# 07_eMMC.net
KiCad netlist of a schematic drawn in Altium Designer
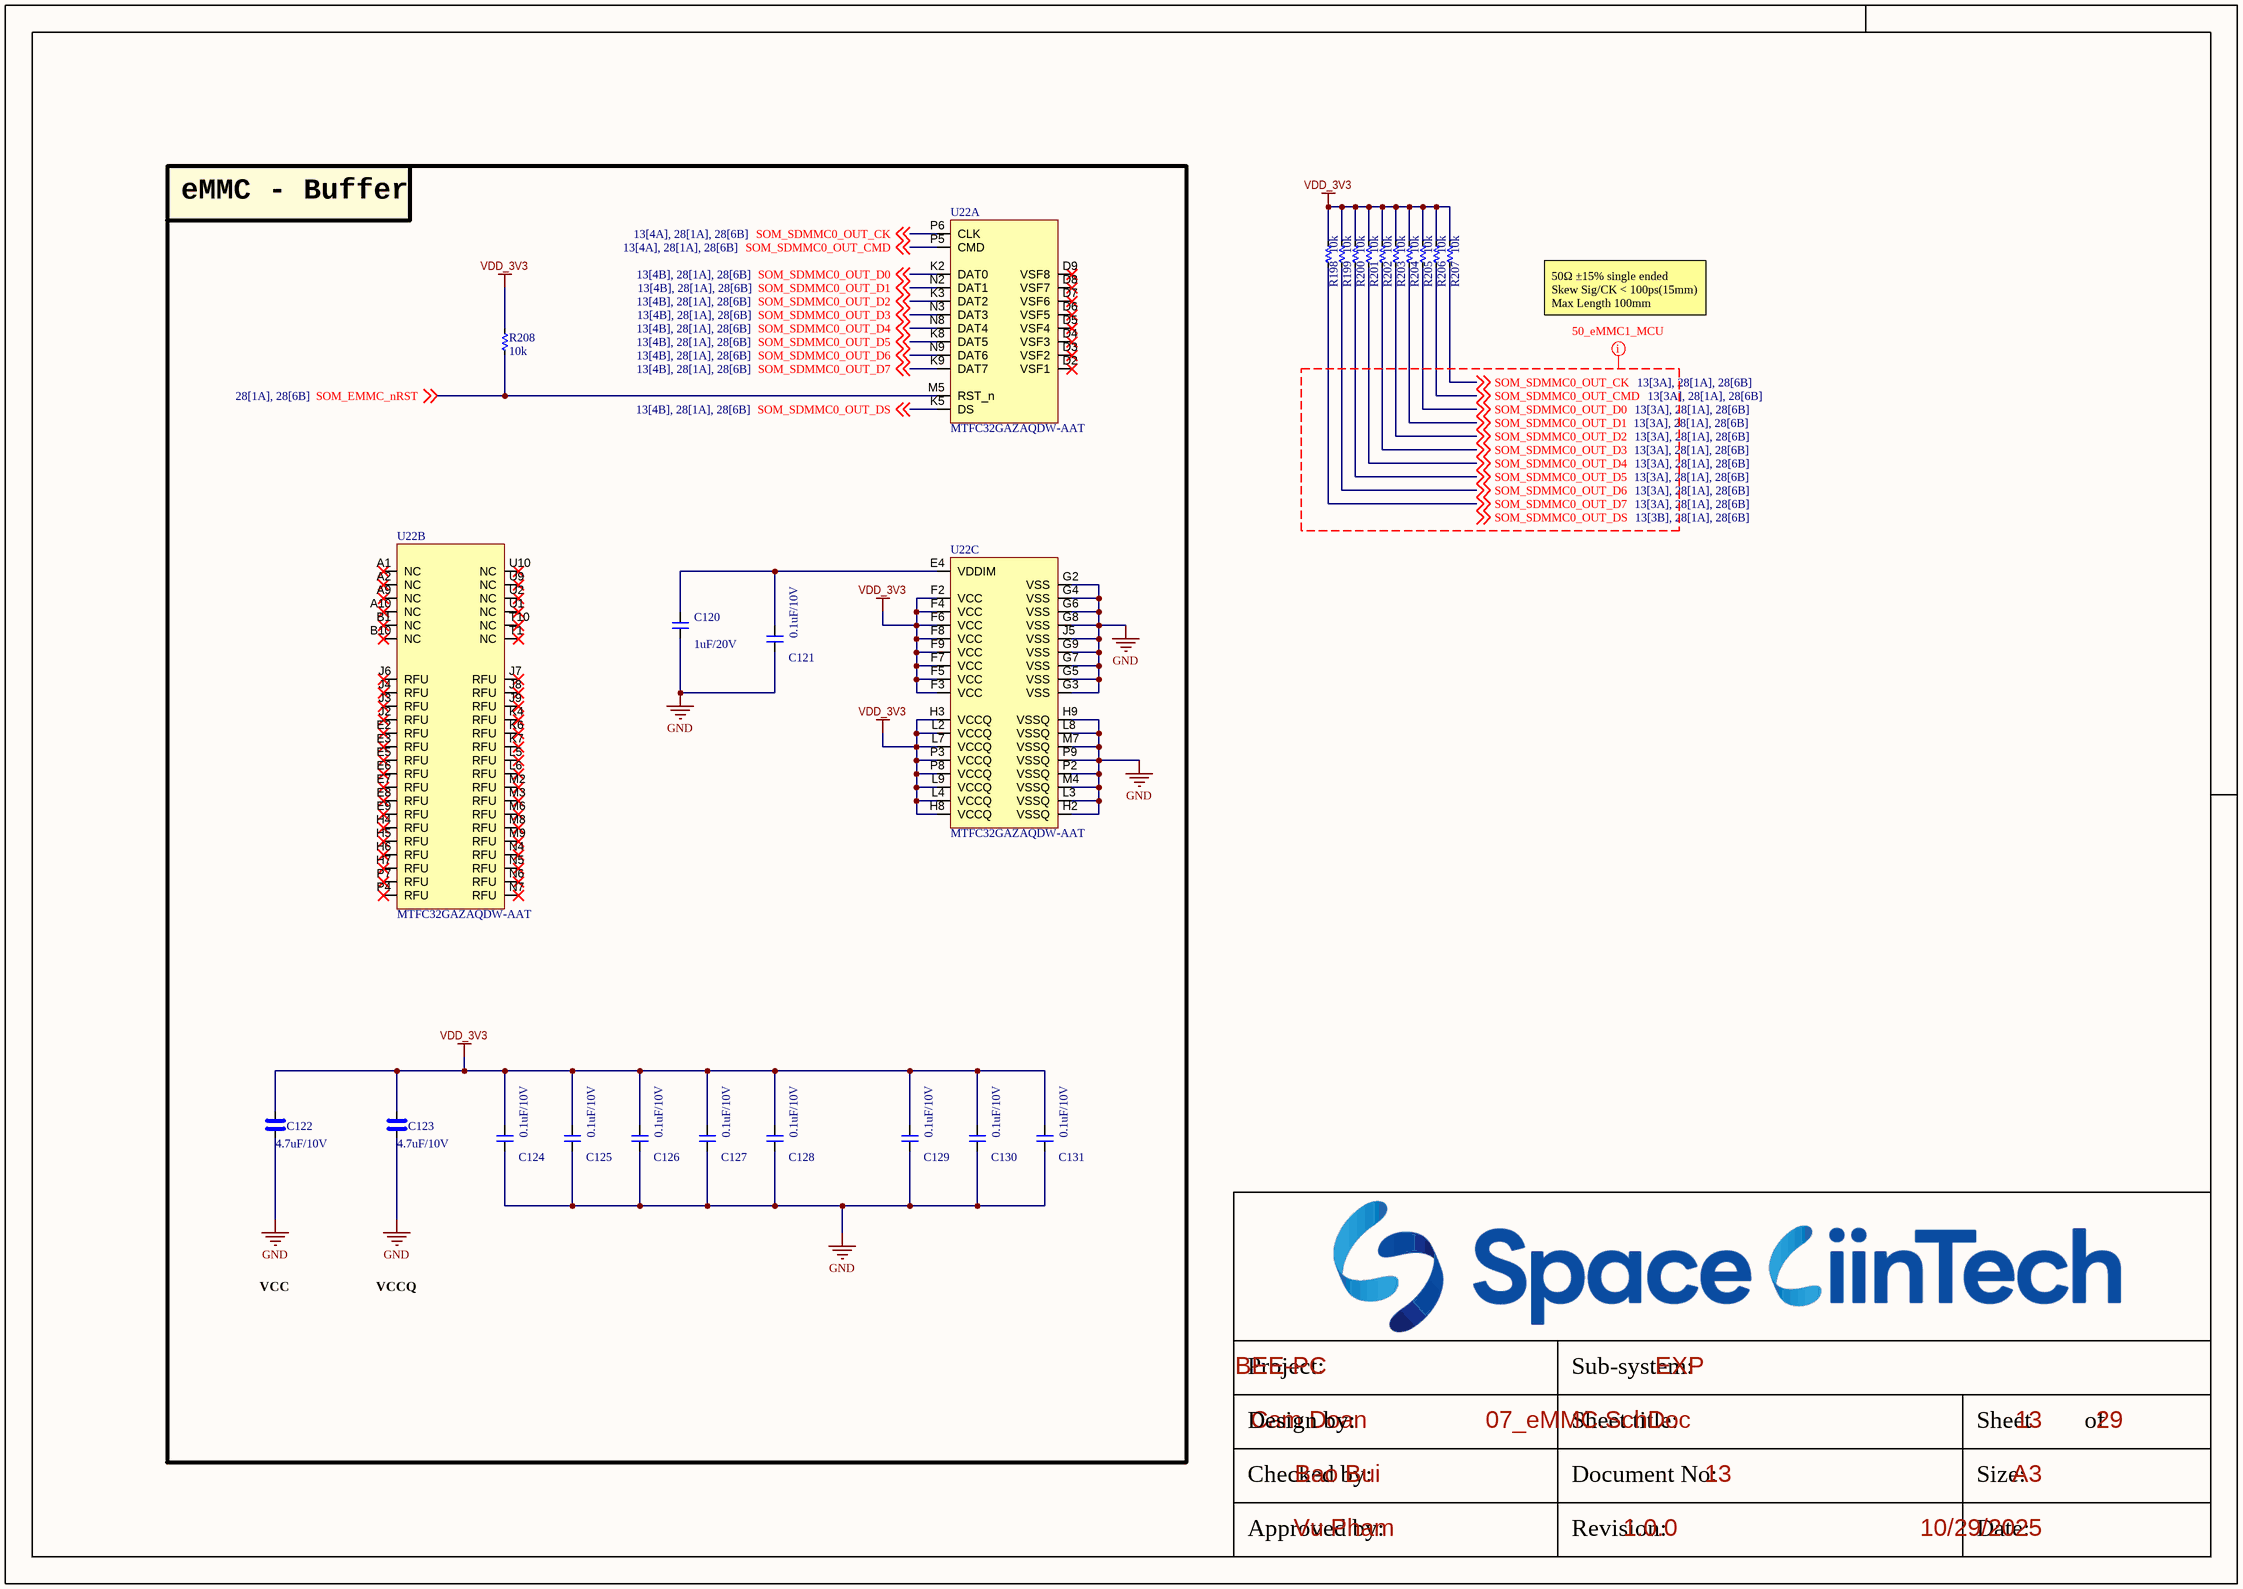
[diagram p0: 07_eMMC.SchDoc]

(export (version "E")
  (design (tool "Eeschema 10.0.6"))
  (components
    (comp (ref "C120")
      (value "1uF/20V")
      (footprint "CAP_C_1005X60")
      (description "CAP CHIP")
      (libsource (lib "LABLIB") (part "_CAP_C_2"))
    )
    (comp (ref "C121")
      (value "0.1uF/10V")
      (footprint "CAP_C_1005X60")
      (description "CAP CHIP")
      (libsource (lib "LABLIB") (part "_CAP_C_2"))
    )
    (comp (ref "C122")
      (value "4.7uF/10V")
      (footprint "CAP_C_1005X60")
      (description "CAP CHIP High Value")
      (libsource (lib "LABLIB") (part "_CAP_C_High_2"))
    )
    (comp (ref "C123")
      (value "4.7uF/10V")
      (footprint "CAP_C_1005X60")
      (description "CAP CHIP High Value")
      (libsource (lib "LABLIB") (part "_CAP_C_High_2"))
    )
    (comp (ref "C124")
      (value "0.1uF/10V")
      (footprint "CAP_C_1005X60")
      (description "CAP CHIP")
      (libsource (lib "LABLIB") (part "_CAP_C_2"))
    )
    (comp (ref "C125")
      (value "0.1uF/10V")
      (footprint "CAP_C_1005X60")
      (description "CAP CHIP")
      (libsource (lib "LABLIB") (part "_CAP_C_2"))
    )
    (comp (ref "C126")
      (value "0.1uF/10V")
      (footprint "CAP_C_1005X60")
      (description "CAP CHIP")
      (libsource (lib "LABLIB") (part "_CAP_C_2"))
    )
    (comp (ref "C127")
      (value "0.1uF/10V")
      (footprint "CAP_C_1005X60")
      (description "CAP CHIP")
      (libsource (lib "LABLIB") (part "_CAP_C_2"))
    )
    (comp (ref "C128")
      (value "0.1uF/10V")
      (footprint "CAP_C_1005X60")
      (description "CAP CHIP")
      (libsource (lib "LABLIB") (part "_CAP_C_2"))
    )
    (comp (ref "C129")
      (value "0.1uF/10V")
      (footprint "CAP_C_1005X60")
      (description "CAP CHIP")
      (libsource (lib "LABLIB") (part "_CAP_C_2"))
    )
    (comp (ref "C130")
      (value "0.1uF/10V")
      (footprint "CAP_C_1005X60")
      (description "CAP CHIP")
      (libsource (lib "LABLIB") (part "_CAP_C_2"))
    )
    (comp (ref "C131")
      (value "0.1uF/10V")
      (footprint "CAP_C_1005X60")
      (description "CAP CHIP")
      (libsource (lib "LABLIB") (part "_CAP_C_2"))
    )
    (comp (ref "R198")
      (value "10k")
      (footprint "RES_C_1005X40")
      (description "RES")
      (libsource (lib "LABLIB") (part "_RES_B_2"))
    )
    (comp (ref "R199")
      (value "10k")
      (footprint "RES_C_1005X40")
      (description "RES")
      (libsource (lib "LABLIB") (part "_RES_B_2"))
    )
    (comp (ref "R200")
      (value "10k")
      (footprint "RES_C_1005X40")
      (description "RES")
      (libsource (lib "LABLIB") (part "_RES_B_2"))
    )
    (comp (ref "R201")
      (value "10k")
      (footprint "RES_C_1005X40")
      (description "RES")
      (libsource (lib "LABLIB") (part "_RES_B_2"))
    )
    (comp (ref "R202")
      (value "10k")
      (footprint "RES_C_1005X40")
      (description "RES")
      (libsource (lib "LABLIB") (part "_RES_B_2"))
    )
    (comp (ref "R203")
      (value "10k")
      (footprint "RES_C_1005X40")
      (description "RES")
      (libsource (lib "LABLIB") (part "_RES_B_2"))
    )
    (comp (ref "R204")
      (value "10k")
      (footprint "RES_C_1005X40")
      (description "RES")
      (libsource (lib "LABLIB") (part "_RES_B_2"))
    )
    (comp (ref "R205")
      (value "10k")
      (footprint "RES_C_1005X40")
      (description "RES")
      (libsource (lib "LABLIB") (part "_RES_B_2"))
    )
    (comp (ref "R206")
      (value "10k")
      (footprint "RES_C_1005X40")
      (description "RES")
      (libsource (lib "LABLIB") (part "_RES_B_2"))
    )
    (comp (ref "R207")
      (value "10k")
      (footprint "RES_C_1005X40")
      (description "RES")
      (libsource (lib "LABLIB") (part "_RES_B_2"))
    )
    (comp (ref "R208")
      (value "10k")
      (footprint "RES_C_1005X40")
      (description "RES")
      (libsource (lib "LABLIB") (part "_RES_B_2"))
    )
    (comp (ref "U22")
      (value "MTFC32GAZAQDW-AAT")
      (footprint "BGA_100_C_100P_10X17_1400X1800X150")
      (libsource (lib "emmc_nofootprint") (part "MTFC32GAZAQDW-AAT"))
    )
  )
  (nets
    (net (code "1") (name "GND") (class "Default")
      (node (ref "C120") (pin "1") (pinfunction "1_1") (pintype "passive"))
      (node (ref "C121") (pin "1") (pinfunction "1_1") (pintype "passive"))
      (node (ref "C122") (pin "1") (pinfunction "1_1") (pintype "passive"))
      (node (ref "C123") (pin "1") (pinfunction "1_1") (pintype "passive"))
      (node (ref "C124") (pin "1") (pinfunction "1_1") (pintype "passive"))
      (node (ref "C125") (pin "1") (pinfunction "1_1") (pintype "passive"))
      (node (ref "C126") (pin "1") (pinfunction "1_1") (pintype "passive"))
      (node (ref "C127") (pin "1") (pinfunction "1_1") (pintype "passive"))
      (node (ref "C128") (pin "1") (pinfunction "1_1") (pintype "passive"))
      (node (ref "C129") (pin "1") (pinfunction "1_1") (pintype "passive"))
      (node (ref "C130") (pin "1") (pinfunction "1_1") (pintype "passive"))
      (node (ref "C131") (pin "1") (pinfunction "1_1") (pintype "passive"))
      (node (ref "U22") (pin "G2") (pinfunction "VSS_G2") (pintype "passive"))
      (node (ref "U22") (pin "G3") (pinfunction "VSS_G3") (pintype "passive"))
      (node (ref "U22") (pin "G4") (pinfunction "VSS_G4") (pintype "passive"))
      (node (ref "U22") (pin "G5") (pinfunction "VSS_G5") (pintype "passive"))
      (node (ref "U22") (pin "G6") (pinfunction "VSS_G6") (pintype "passive"))
      (node (ref "U22") (pin "G7") (pinfunction "VSS_G7") (pintype "passive"))
      (node (ref "U22") (pin "G8") (pinfunction "VSS_G8") (pintype "passive"))
      (node (ref "U22") (pin "G9") (pinfunction "VSS_G9") (pintype "passive"))
      (node (ref "U22") (pin "H2") (pinfunction "VSSQ_H2") (pintype "passive"))
      (node (ref "U22") (pin "H9") (pinfunction "VSSQ_H9") (pintype "passive"))
      (node (ref "U22") (pin "J5") (pinfunction "VSS_J5") (pintype "passive"))
      (node (ref "U22") (pin "L3") (pinfunction "VSSQ_L3") (pintype "passive"))
      (node (ref "U22") (pin "L8") (pinfunction "VSSQ_L8") (pintype "passive"))
      (node (ref "U22") (pin "M4") (pinfunction "VSSQ_M4") (pintype "passive"))
      (node (ref "U22") (pin "M7") (pinfunction "VSSQ_M7") (pintype "passive"))
      (node (ref "U22") (pin "P2") (pinfunction "VSSQ_P2") (pintype "passive"))
      (node (ref "U22") (pin "P9") (pinfunction "VSSQ_P9") (pintype "passive"))
    )
    (net (code "2") (name "Net-(U22C-VDDIM)") (class "Default")
      (node (ref "C120") (pin "2") (pinfunction "2_2") (pintype "passive"))
      (node (ref "C121") (pin "2") (pinfunction "2_2") (pintype "passive"))
      (node (ref "U22") (pin "E4") (pinfunction "VDDIM_E4") (pintype "passive"))
    )
    (net (code "3") (name "SOM_EMMC_nRST") (class "Default")
      (node (ref "R208") (pin "1") (pinfunction "1_1") (pintype "passive"))
      (node (ref "U22") (pin "M5") (pinfunction "RST_n_M5") (pintype "passive"))
    )
    (net (code "4") (name "SOM_SDMMC0_OUT_CK") (class "Default")
      (node (ref "R207") (pin "1") (pinfunction "1_1") (pintype "passive"))
      (node (ref "U22") (pin "P6") (pinfunction "CLK_P6") (pintype "passive"))
    )
    (net (code "5") (name "SOM_SDMMC0_OUT_CMD") (class "Default")
      (node (ref "R206") (pin "1") (pinfunction "1_1") (pintype "passive"))
      (node (ref "U22") (pin "P5") (pinfunction "CMD_P5") (pintype "passive"))
    )
    (net (code "6") (name "SOM_SDMMC0_OUT_D0") (class "Default")
      (node (ref "R205") (pin "1") (pinfunction "1_1") (pintype "passive"))
      (node (ref "U22") (pin "K2") (pinfunction "DAT0_K2") (pintype "passive"))
    )
    (net (code "7") (name "SOM_SDMMC0_OUT_D1") (class "Default")
      (node (ref "R204") (pin "1") (pinfunction "1_1") (pintype "passive"))
      (node (ref "U22") (pin "N2") (pinfunction "DAT1_N2") (pintype "passive"))
    )
    (net (code "8") (name "SOM_SDMMC0_OUT_D2") (class "Default")
      (node (ref "R203") (pin "1") (pinfunction "1_1") (pintype "passive"))
      (node (ref "U22") (pin "K3") (pinfunction "DAT2_K3") (pintype "passive"))
    )
    (net (code "9") (name "SOM_SDMMC0_OUT_D3") (class "Default")
      (node (ref "R202") (pin "1") (pinfunction "1_1") (pintype "passive"))
      (node (ref "U22") (pin "N3") (pinfunction "DAT3_N3") (pintype "passive"))
    )
    (net (code "10") (name "SOM_SDMMC0_OUT_D4") (class "Default")
      (node (ref "R201") (pin "1") (pinfunction "1_1") (pintype "passive"))
      (node (ref "U22") (pin "N8") (pinfunction "DAT4_N8") (pintype "passive"))
    )
    (net (code "11") (name "SOM_SDMMC0_OUT_D5") (class "Default")
      (node (ref "R200") (pin "1") (pinfunction "1_1") (pintype "passive"))
      (node (ref "U22") (pin "K8") (pinfunction "DAT5_K8") (pintype "passive"))
    )
    (net (code "12") (name "SOM_SDMMC0_OUT_D6") (class "Default")
      (node (ref "R199") (pin "1") (pinfunction "1_1") (pintype "passive"))
      (node (ref "U22") (pin "N9") (pinfunction "DAT6_N9") (pintype "passive"))
    )
    (net (code "13") (name "SOM_SDMMC0_OUT_D7") (class "Default")
      (node (ref "R198") (pin "1") (pinfunction "1_1") (pintype "passive"))
      (node (ref "U22") (pin "K9") (pinfunction "DAT7_K9") (pintype "passive"))
    )
    (net (code "14") (name "SOM_SDMMC0_OUT_DS") (class "Default")
      (node (ref "U22") (pin "K5") (pinfunction "DS_K5") (pintype "passive"))
    )
    (net (code "15") (name "VDD_3V3") (class "Default")
      (node (ref "C122") (pin "2") (pinfunction "2_2") (pintype "passive"))
      (node (ref "C123") (pin "2") (pinfunction "2_2") (pintype "passive"))
      (node (ref "C124") (pin "2") (pinfunction "2_2") (pintype "passive"))
      (node (ref "C125") (pin "2") (pinfunction "2_2") (pintype "passive"))
      (node (ref "C126") (pin "2") (pinfunction "2_2") (pintype "passive"))
      (node (ref "C127") (pin "2") (pinfunction "2_2") (pintype "passive"))
      (node (ref "C128") (pin "2") (pinfunction "2_2") (pintype "passive"))
      (node (ref "C129") (pin "2") (pinfunction "2_2") (pintype "passive"))
      (node (ref "C130") (pin "2") (pinfunction "2_2") (pintype "passive"))
      (node (ref "C131") (pin "2") (pinfunction "2_2") (pintype "passive"))
      (node (ref "R198") (pin "2") (pinfunction "2_2") (pintype "passive"))
      (node (ref "R199") (pin "2") (pinfunction "2_2") (pintype "passive"))
      (node (ref "R200") (pin "2") (pinfunction "2_2") (pintype "passive"))
      (node (ref "R201") (pin "2") (pinfunction "2_2") (pintype "passive"))
      (node (ref "R202") (pin "2") (pinfunction "2_2") (pintype "passive"))
      (node (ref "R203") (pin "2") (pinfunction "2_2") (pintype "passive"))
      (node (ref "R204") (pin "2") (pinfunction "2_2") (pintype "passive"))
      (node (ref "R205") (pin "2") (pinfunction "2_2") (pintype "passive"))
      (node (ref "R206") (pin "2") (pinfunction "2_2") (pintype "passive"))
      (node (ref "R207") (pin "2") (pinfunction "2_2") (pintype "passive"))
      (node (ref "R208") (pin "2") (pinfunction "2_2") (pintype "passive"))
      (node (ref "U22") (pin "F2") (pinfunction "VCC_F2") (pintype "passive"))
      (node (ref "U22") (pin "F3") (pinfunction "VCC_F3") (pintype "passive"))
      (node (ref "U22") (pin "F4") (pinfunction "VCC_F4") (pintype "passive"))
      (node (ref "U22") (pin "F5") (pinfunction "VCC_F5") (pintype "passive"))
      (node (ref "U22") (pin "F6") (pinfunction "VCC_F6") (pintype "passive"))
      (node (ref "U22") (pin "F7") (pinfunction "VCC_F7") (pintype "passive"))
      (node (ref "U22") (pin "F8") (pinfunction "VCC_F8") (pintype "passive"))
      (node (ref "U22") (pin "F9") (pinfunction "VCC_F9") (pintype "passive"))
      (node (ref "U22") (pin "H3") (pinfunction "VCCQ_H3") (pintype "passive"))
      (node (ref "U22") (pin "H8") (pinfunction "VCCQ_H8") (pintype "passive"))
      (node (ref "U22") (pin "L2") (pinfunction "VCCQ_L2") (pintype "passive"))
      (node (ref "U22") (pin "L4") (pinfunction "VCCQ_L4") (pintype "passive"))
      (node (ref "U22") (pin "L7") (pinfunction "VCCQ_L7") (pintype "passive"))
      (node (ref "U22") (pin "L9") (pinfunction "VCCQ_L9") (pintype "passive"))
      (node (ref "U22") (pin "P3") (pinfunction "VCCQ_P3") (pintype "passive"))
      (node (ref "U22") (pin "P8") (pinfunction "VCCQ_P8") (pintype "passive"))
    )
    (net (code "16") (name "unconnected-(U22A-VSF1-PadD2)") (class "Default")
      (node (ref "U22") (pin "D2") (pinfunction "VSF1_D2") (pintype "passive+no_connect"))
    )
    (net (code "17") (name "unconnected-(U22A-VSF2-PadD3)") (class "Default")
      (node (ref "U22") (pin "D3") (pinfunction "VSF2_D3") (pintype "passive+no_connect"))
    )
    (net (code "18") (name "unconnected-(U22A-VSF3-PadD4)") (class "Default")
      (node (ref "U22") (pin "D4") (pinfunction "VSF3_D4") (pintype "passive+no_connect"))
    )
    (net (code "19") (name "unconnected-(U22A-VSF4-PadD5)") (class "Default")
      (node (ref "U22") (pin "D5") (pinfunction "VSF4_D5") (pintype "passive+no_connect"))
    )
    (net (code "20") (name "unconnected-(U22A-VSF5-PadD6)") (class "Default")
      (node (ref "U22") (pin "D6") (pinfunction "VSF5_D6") (pintype "passive+no_connect"))
    )
    (net (code "21") (name "unconnected-(U22A-VSF6-PadD7)") (class "Default")
      (node (ref "U22") (pin "D7") (pinfunction "VSF6_D7") (pintype "passive+no_connect"))
    )
    (net (code "22") (name "unconnected-(U22A-VSF7-PadD8)") (class "Default")
      (node (ref "U22") (pin "D8") (pinfunction "VSF7_D8") (pintype "passive+no_connect"))
    )
    (net (code "23") (name "unconnected-(U22A-VSF8-PadD9)") (class "Default")
      (node (ref "U22") (pin "D9") (pinfunction "VSF8_D9") (pintype "passive+no_connect"))
    )
    (net (code "24") (name "unconnected-(U22B-NC-PadA1)") (class "Default")
      (node (ref "U22") (pin "A1") (pinfunction "NC_A1") (pintype "passive+no_connect"))
    )
    (net (code "25") (name "unconnected-(U22B-NC-PadA2)") (class "Default")
      (node (ref "U22") (pin "A2") (pinfunction "NC_A2") (pintype "passive+no_connect"))
    )
    (net (code "26") (name "unconnected-(U22B-NC-PadA9)") (class "Default")
      (node (ref "U22") (pin "A9") (pinfunction "NC_A9") (pintype "passive+no_connect"))
    )
    (net (code "27") (name "unconnected-(U22B-NC-PadA10)") (class "Default")
      (node (ref "U22") (pin "A10") (pinfunction "NC_A10") (pintype "passive+no_connect"))
    )
    (net (code "28") (name "unconnected-(U22B-NC-PadB1)") (class "Default")
      (node (ref "U22") (pin "B1") (pinfunction "NC_B1") (pintype "passive+no_connect"))
    )
    (net (code "29") (name "unconnected-(U22B-NC-PadB10)") (class "Default")
      (node (ref "U22") (pin "B10") (pinfunction "NC_B10") (pintype "passive+no_connect"))
    )
    (net (code "30") (name "unconnected-(U22B-NC-PadT1)") (class "Default")
      (node (ref "U22") (pin "T1") (pinfunction "NC_T1") (pintype "passive+no_connect"))
    )
    (net (code "31") (name "unconnected-(U22B-NC-PadT10)") (class "Default")
      (node (ref "U22") (pin "T10") (pinfunction "NC_T10") (pintype "passive+no_connect"))
    )
    (net (code "32") (name "unconnected-(U22B-NC-PadU1)") (class "Default")
      (node (ref "U22") (pin "U1") (pinfunction "NC_U1") (pintype "passive+no_connect"))
    )
    (net (code "33") (name "unconnected-(U22B-NC-PadU2)") (class "Default")
      (node (ref "U22") (pin "U2") (pinfunction "NC_U2") (pintype "passive+no_connect"))
    )
    (net (code "34") (name "unconnected-(U22B-NC-PadU9)") (class "Default")
      (node (ref "U22") (pin "U9") (pinfunction "NC_U9") (pintype "passive+no_connect"))
    )
    (net (code "35") (name "unconnected-(U22B-NC-PadU10)") (class "Default")
      (node (ref "U22") (pin "U10") (pinfunction "NC_U10") (pintype "passive+no_connect"))
    )
    (net (code "36") (name "unconnected-(U22B-RFU-PadE2)") (class "Default")
      (node (ref "U22") (pin "E2") (pinfunction "RFU_E2") (pintype "passive+no_connect"))
    )
    (net (code "37") (name "unconnected-(U22B-RFU-PadE3)") (class "Default")
      (node (ref "U22") (pin "E3") (pinfunction "RFU_E3") (pintype "passive+no_connect"))
    )
    (net (code "38") (name "unconnected-(U22B-RFU-PadE5)") (class "Default")
      (node (ref "U22") (pin "E5") (pinfunction "RFU_E5") (pintype "passive+no_connect"))
    )
    (net (code "39") (name "unconnected-(U22B-RFU-PadE6)") (class "Default")
      (node (ref "U22") (pin "E6") (pinfunction "RFU_E6") (pintype "passive+no_connect"))
    )
    (net (code "40") (name "unconnected-(U22B-RFU-PadE7)") (class "Default")
      (node (ref "U22") (pin "E7") (pinfunction "RFU_E7") (pintype "passive+no_connect"))
    )
    (net (code "41") (name "unconnected-(U22B-RFU-PadE8)") (class "Default")
      (node (ref "U22") (pin "E8") (pinfunction "RFU_E8") (pintype "passive+no_connect"))
    )
    (net (code "42") (name "unconnected-(U22B-RFU-PadE9)") (class "Default")
      (node (ref "U22") (pin "E9") (pinfunction "RFU_E9") (pintype "passive+no_connect"))
    )
    (net (code "43") (name "unconnected-(U22B-RFU-PadH4)") (class "Default")
      (node (ref "U22") (pin "H4") (pinfunction "RFU_H4") (pintype "passive+no_connect"))
    )
    (net (code "44") (name "unconnected-(U22B-RFU-PadH5)") (class "Default")
      (node (ref "U22") (pin "H5") (pinfunction "RFU_H5") (pintype "passive+no_connect"))
    )
    (net (code "45") (name "unconnected-(U22B-RFU-PadH6)") (class "Default")
      (node (ref "U22") (pin "H6") (pinfunction "RFU_H6") (pintype "passive+no_connect"))
    )
    (net (code "46") (name "unconnected-(U22B-RFU-PadH7)") (class "Default")
      (node (ref "U22") (pin "H7") (pinfunction "RFU_H7") (pintype "passive+no_connect"))
    )
    (net (code "47") (name "unconnected-(U22B-RFU-PadJ2)") (class "Default")
      (node (ref "U22") (pin "J2") (pinfunction "RFU_J2") (pintype "passive+no_connect"))
    )
    (net (code "48") (name "unconnected-(U22B-RFU-PadJ3)") (class "Default")
      (node (ref "U22") (pin "J3") (pinfunction "RFU_J3") (pintype "passive+no_connect"))
    )
    (net (code "49") (name "unconnected-(U22B-RFU-PadJ4)") (class "Default")
      (node (ref "U22") (pin "J4") (pinfunction "RFU_J4") (pintype "passive+no_connect"))
    )
    (net (code "50") (name "unconnected-(U22B-RFU-PadJ6)") (class "Default")
      (node (ref "U22") (pin "J6") (pinfunction "RFU_J6") (pintype "passive+no_connect"))
    )
    (net (code "51") (name "unconnected-(U22B-RFU-PadJ7)") (class "Default")
      (node (ref "U22") (pin "J7") (pinfunction "RFU_J7") (pintype "passive+no_connect"))
    )
    (net (code "52") (name "unconnected-(U22B-RFU-PadJ8)") (class "Default")
      (node (ref "U22") (pin "J8") (pinfunction "RFU_J8") (pintype "passive+no_connect"))
    )
    (net (code "53") (name "unconnected-(U22B-RFU-PadJ9)") (class "Default")
      (node (ref "U22") (pin "J9") (pinfunction "RFU_J9") (pintype "passive+no_connect"))
    )
    (net (code "54") (name "unconnected-(U22B-RFU-PadK4)") (class "Default")
      (node (ref "U22") (pin "K4") (pinfunction "RFU_K4") (pintype "passive+no_connect"))
    )
    (net (code "55") (name "unconnected-(U22B-RFU-PadK6)") (class "Default")
      (node (ref "U22") (pin "K6") (pinfunction "RFU_K6") (pintype "passive+no_connect"))
    )
    (net (code "56") (name "unconnected-(U22B-RFU-PadK7)") (class "Default")
      (node (ref "U22") (pin "K7") (pinfunction "RFU_K7") (pintype "passive+no_connect"))
    )
    (net (code "57") (name "unconnected-(U22B-RFU-PadL5)") (class "Default")
      (node (ref "U22") (pin "L5") (pinfunction "RFU_L5") (pintype "passive+no_connect"))
    )
    (net (code "58") (name "unconnected-(U22B-RFU-PadL6)") (class "Default")
      (node (ref "U22") (pin "L6") (pinfunction "RFU_L6") (pintype "passive+no_connect"))
    )
    (net (code "59") (name "unconnected-(U22B-RFU-PadM2)") (class "Default")
      (node (ref "U22") (pin "M2") (pinfunction "RFU_M2") (pintype "passive+no_connect"))
    )
    (net (code "60") (name "unconnected-(U22B-RFU-PadM3)") (class "Default")
      (node (ref "U22") (pin "M3") (pinfunction "RFU_M3") (pintype "passive+no_connect"))
    )
    (net (code "61") (name "unconnected-(U22B-RFU-PadM6)") (class "Default")
      (node (ref "U22") (pin "M6") (pinfunction "RFU_M6") (pintype "passive+no_connect"))
    )
    (net (code "62") (name "unconnected-(U22B-RFU-PadM8)") (class "Default")
      (node (ref "U22") (pin "M8") (pinfunction "RFU_M8") (pintype "passive+no_connect"))
    )
    (net (code "63") (name "unconnected-(U22B-RFU-PadM9)") (class "Default")
      (node (ref "U22") (pin "M9") (pinfunction "RFU_M9") (pintype "passive+no_connect"))
    )
    (net (code "64") (name "unconnected-(U22B-RFU-PadN4)") (class "Default")
      (node (ref "U22") (pin "N4") (pinfunction "RFU_N4") (pintype "passive+no_connect"))
    )
    (net (code "65") (name "unconnected-(U22B-RFU-PadN5)") (class "Default")
      (node (ref "U22") (pin "N5") (pinfunction "RFU_N5") (pintype "passive+no_connect"))
    )
    (net (code "66") (name "unconnected-(U22B-RFU-PadN6)") (class "Default")
      (node (ref "U22") (pin "N6") (pinfunction "RFU_N6") (pintype "passive+no_connect"))
    )
    (net (code "67") (name "unconnected-(U22B-RFU-PadN7)") (class "Default")
      (node (ref "U22") (pin "N7") (pinfunction "RFU_N7") (pintype "passive+no_connect"))
    )
    (net (code "68") (name "unconnected-(U22B-RFU-PadP4)") (class "Default")
      (node (ref "U22") (pin "P4") (pinfunction "RFU_P4") (pintype "passive+no_connect"))
    )
    (net (code "69") (name "unconnected-(U22B-RFU-PadP7)") (class "Default")
      (node (ref "U22") (pin "P7") (pinfunction "RFU_P7") (pintype "passive+no_connect"))
    )
  )
)
